# brick_i2c_proximity_mini.net
KiCad netlist of a schematic drawn in EAGLE
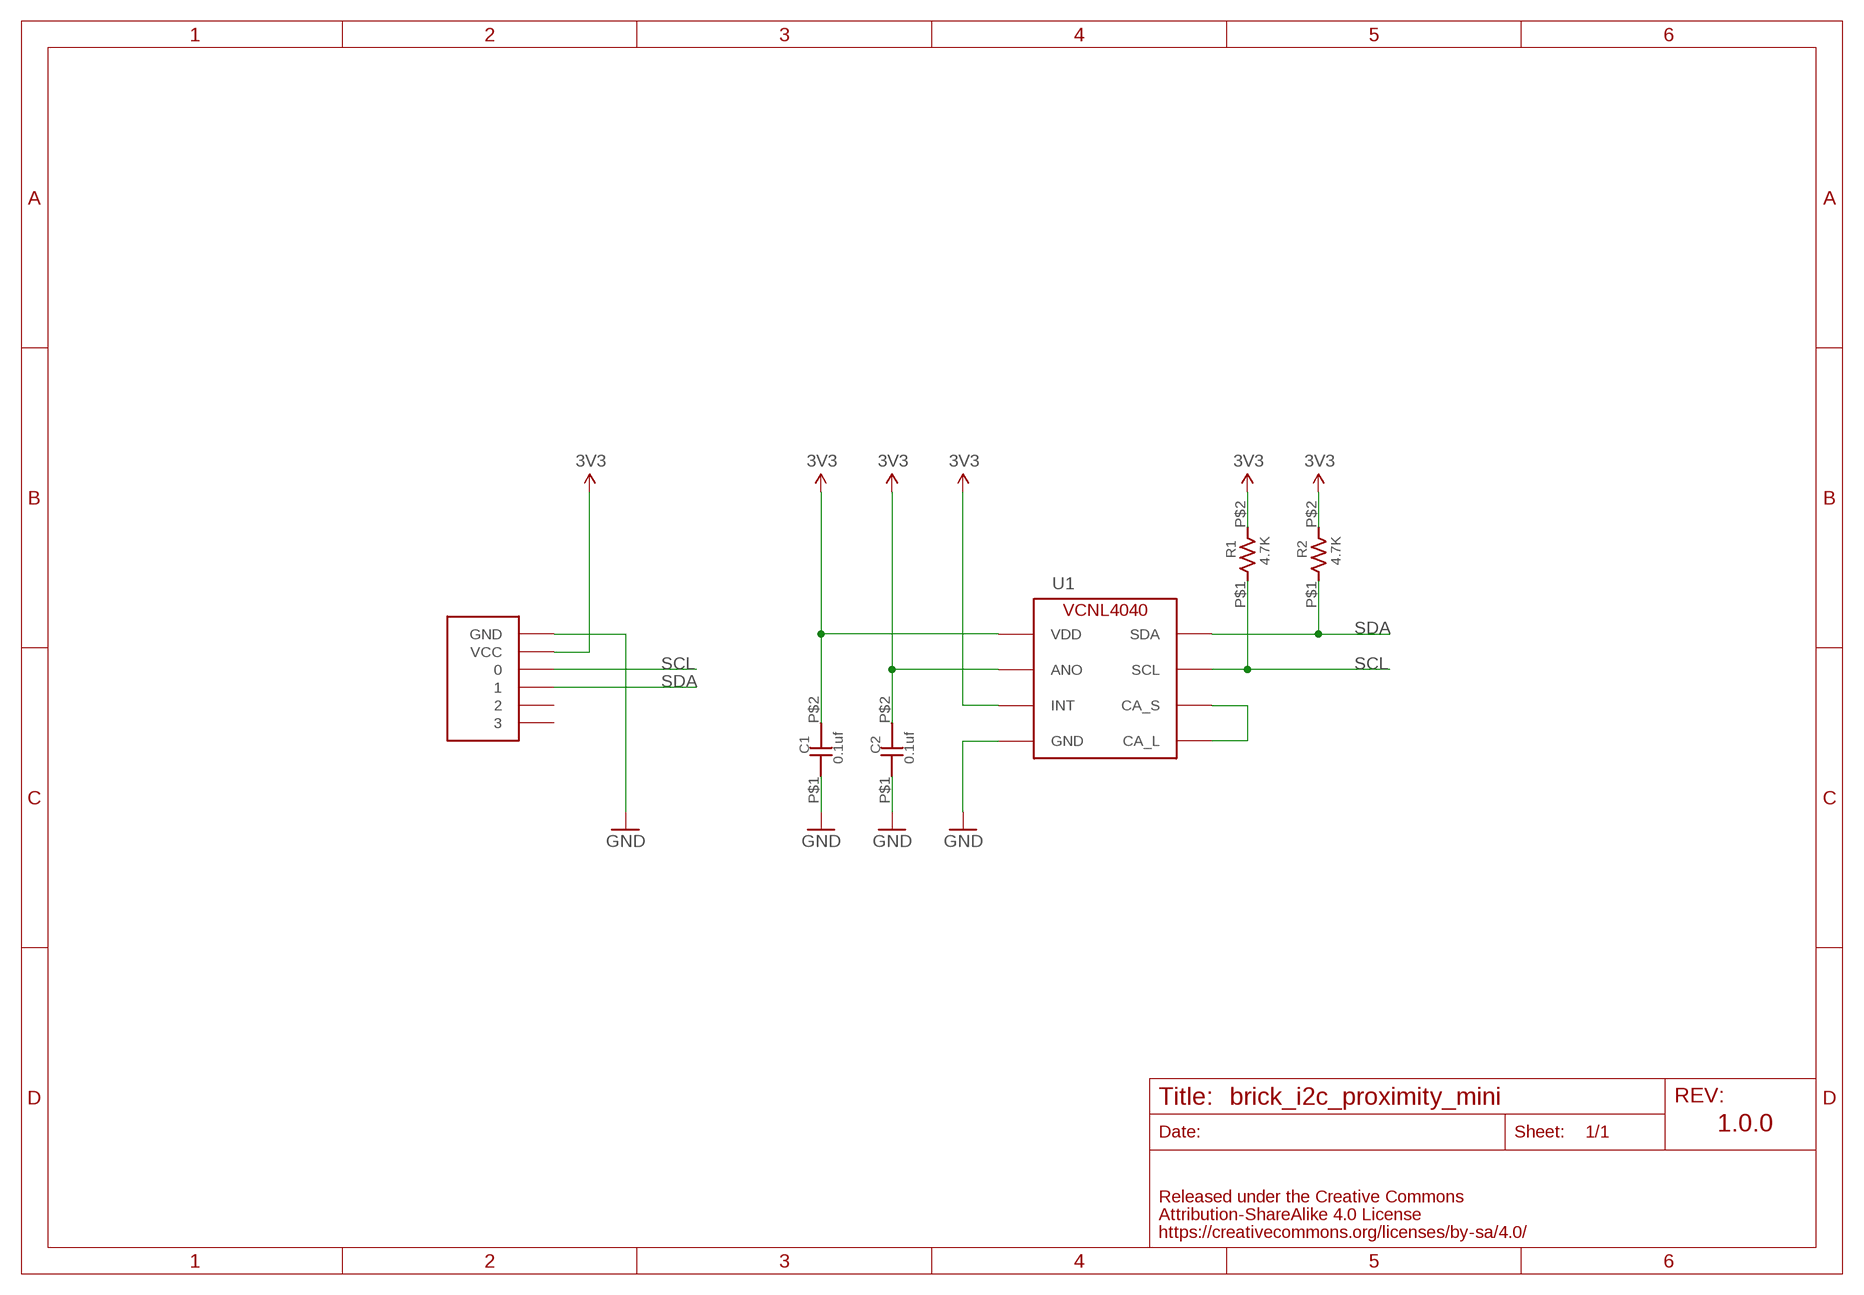
[diagram p0: schematic, sheet 1]

(export (version "E")
  (design (tool "Eeschema 10.0.6"))
  (components
    (comp (ref "C1")
      (value "0.1uf")
      (footprint "eagle-import:0402")
      (libsource (lib "eagle-import") (part "0402"))
    )
    (comp (ref "C2")
      (value "0.1uf")
      (footprint "eagle-import:0402")
      (libsource (lib "eagle-import") (part "0402"))
    )
    (comp (ref "R1")
      (value "4.7K")
      (footprint "eagle-import:0402")
      (libsource (lib "eagle-import") (part "FaBo-Resistors_0402"))
    )
    (comp (ref "R2")
      (value "4.7K")
      (footprint "eagle-import:0402")
      (libsource (lib "eagle-import") (part "FaBo-Resistors_0402"))
    )
    (comp (ref "U$2")
      (value "FABO-NANO")
      (footprint "eagle-import:FABO-NANO")
      (libsource (lib "eagle-import") (part "FABO-NANO"))
    )
    (comp (ref "U1")
      (value "VCNL4040M3OE")
      (footprint "eagle-import:VCNL4040M3OE")
      (libsource (lib "eagle-import") (part "VCNL4040M3OE"))
    )
  )
  (nets
    (net (code "1") (name "/SCL") (class "Default")
      (node (ref "R1") (pin "P$1") (pinfunction "1_P$1") (pintype "passive"))
      (node (ref "U$2") (pin "0") (pinfunction "0_0") (pintype "bidirectional"))
      (node (ref "U1") (pin "8") (pinfunction "SCL_8") (pintype "bidirectional"))
    )
    (net (code "2") (name "/SDA") (class "Default")
      (node (ref "R2") (pin "P$1") (pinfunction "1_P$1") (pintype "passive"))
      (node (ref "U$2") (pin "1") (pinfunction "1_1") (pintype "bidirectional"))
      (node (ref "U1") (pin "7") (pinfunction "SDA_7") (pintype "bidirectional"))
    )
    (net (code "3") (name "3V3") (class "Default")
      (node (ref "C1") (pin "P$2") (pinfunction "2_P$2") (pintype "passive"))
      (node (ref "C2") (pin "P$2") (pinfunction "2_P$2") (pintype "passive"))
      (node (ref "R1") (pin "P$2") (pinfunction "2_P$2") (pintype "passive"))
      (node (ref "R2") (pin "P$2") (pinfunction "2_P$2") (pintype "passive"))
      (node (ref "U$2") (pin "VCC") (pinfunction "VCC_VCC") (pintype "bidirectional"))
      (node (ref "U1") (pin "3") (pinfunction "VDD_3") (pintype "bidirectional"))
      (node (ref "U1") (pin "4") (pinfunction "ANO_4") (pintype "bidirectional"))
      (node (ref "U1") (pin "6") (pinfunction "INT_6") (pintype "bidirectional"))
    )
    (net (code "4") (name "GND") (class "Default")
      (node (ref "C1") (pin "P$1") (pinfunction "1_P$1") (pintype "passive"))
      (node (ref "C2") (pin "P$1") (pinfunction "1_P$1") (pintype "passive"))
      (node (ref "U$2") (pin "GND") (pinfunction "GND_GND") (pintype "bidirectional"))
      (node (ref "U1") (pin "1") (pinfunction "GND_1") (pintype "bidirectional"))
    )
    (net (code "5") (name "Net-(U1-CA_L)") (class "Default")
      (node (ref "U1") (pin "2") (pinfunction "CA_S_2") (pintype "bidirectional"))
      (node (ref "U1") (pin "5") (pinfunction "CA_L_5") (pintype "bidirectional"))
    )
    (net (code "6") (name "unconnected-(U$2-Pad2)") (class "Default")
      (node (ref "U$2") (pin "2") (pinfunction "2_2") (pintype "bidirectional"))
    )
    (net (code "7") (name "unconnected-(U$2-Pad3)") (class "Default")
      (node (ref "U$2") (pin "3") (pinfunction "3_3") (pintype "bidirectional"))
    )
  )
)
